# 9040_fm.net
KiCad netlist of a schematic drawn in Altium Designer
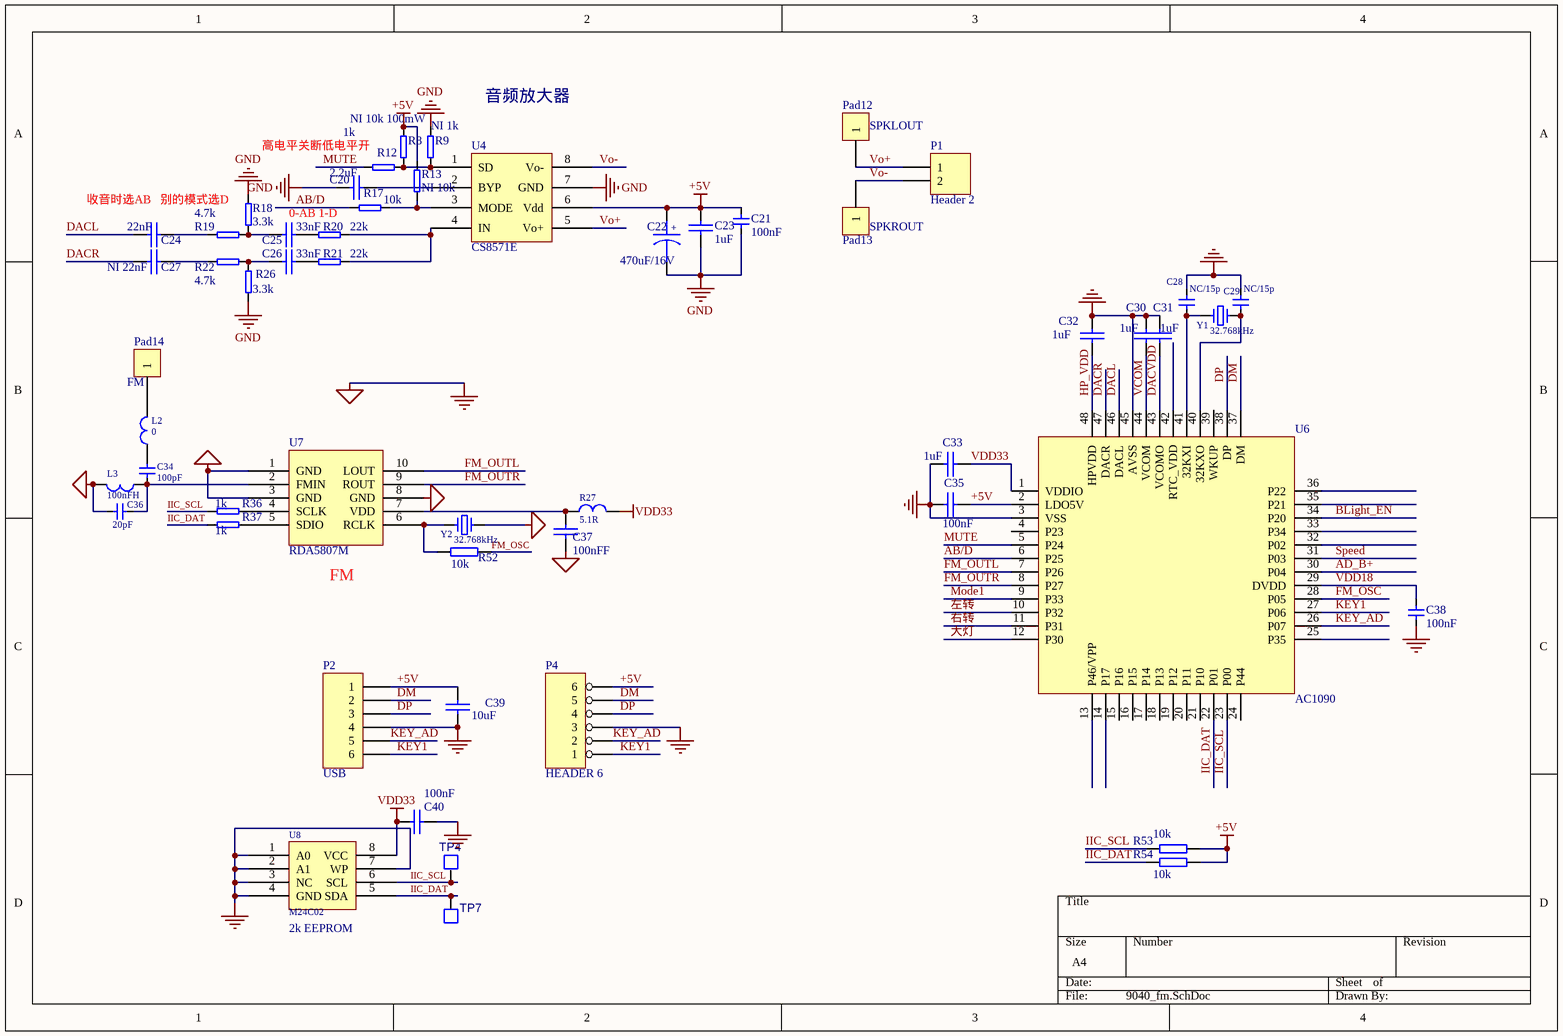
[diagram p0: 9040_fm.SchDoc]

(export (version "E")
  (design (tool "Eeschema 10.0.6"))
  (components
    (comp (ref "C20")
      (value "2.2uF")
      (footprint "0805")
      (description "Capacitor")
      (libsource (lib "") (part "CAP_1"))
    )
    (comp (ref "C21")
      (value "100nF")
      (footprint "0805")
      (description "Capacitor")
      (libsource (lib "*") (part "CAP"))
    )
    (comp (ref "C22")
      (value "470uF/16V")
      (footprint "RB.1/.2")
      (description "Capacitor")
      (libsource (lib "*") (part "CAPACITOR POL"))
    )
    (comp (ref "C23")
      (value "1uF")
      (footprint "0805")
      (description "Capacitor")
      (libsource (lib "") (part "CAP_1"))
    )
    (comp (ref "C24")
      (value "22nF")
      (footprint "0805")
      (description "Capacitor")
      (libsource (lib "") (part "CAP_1"))
    )
    (comp (ref "C25")
      (value "33nF")
      (footprint "0805")
      (description "Capacitor")
      (libsource (lib "") (part "CAP_1"))
    )
    (comp (ref "C26")
      (value "33nF")
      (footprint "0805")
      (description "Capacitor")
      (libsource (lib "") (part "CAP_1"))
    )
    (comp (ref "C27")
      (value "NI 22nF")
      (footprint "0805")
      (description "Capacitor")
      (libsource (lib "") (part "CAP_1"))
    )
    (comp (ref "C28")
      (value "NC/15p")
      (footprint "0603")
      (description "Capacitor")
      (libsource (lib "*") (part "CAP"))
    )
    (comp (ref "C29")
      (value "NC/15p")
      (footprint "0603")
      (description "Capacitor")
      (libsource (lib "*") (part "CAP"))
    )
    (comp (ref "C30")
      (value "1uF")
      (footprint "0805")
      (description "Capacitor")
      (libsource (lib "") (part "CAP_1"))
    )
    (comp (ref "C31")
      (value "1uF")
      (footprint "0805")
      (description "Capacitor")
      (libsource (lib "") (part "CAP_1"))
    )
    (comp (ref "C32")
      (value "1uF")
      (footprint "0805")
      (description "Capacitor")
      (libsource (lib "") (part "CAP_1"))
    )
    (comp (ref "C33")
      (value "1uF")
      (footprint "0805")
      (description "Capacitor")
      (libsource (lib "") (part "CAP_1"))
    )
    (comp (ref "C34")
      (value "100pF")
      (footprint "0805")
      (description "Capacitor")
      (libsource (lib "") (part "CAP_3"))
    )
    (comp (ref "C35")
      (value "100nF")
      (footprint "0805")
      (description "Capacitor")
      (libsource (lib "") (part "CAP_2"))
    )
    (comp (ref "C36")
      (value "20pF")
      (footprint "0603")
      (description "Capacitor")
      (libsource (lib "") (part "CAP_3"))
    )
    (comp (ref "C37")
      (value "100nFF")
      (footprint "0805")
      (description "Capacitor")
      (libsource (lib "") (part "CAP_1"))
    )
    (comp (ref "C38")
      (value "100nF")
      (footprint "0603")
      (description "Capacitor")
      (libsource (lib "*") (part "CAP"))
    )
    (comp (ref "C39")
      (value "10uF")
      (footprint "0805")
      (description "Capacitor")
      (libsource (lib "") (part "CAP_1"))
    )
    (comp (ref "C40")
      (value "100nF")
      (footprint "0805")
      (description "Capacitor")
      (libsource (lib "") (part "CAP_1"))
    )
    (comp (ref "L2") (value "0") (footprint "0805") (libsource (lib "*") (part "INDUCTOR")))
    (comp (ref "L3") (value "100nFH") (footprint "0603") (libsource (lib "*") (part "INDUCTOR")))
    (comp (ref "P1")
      (value "Header 2")
      (footprint "2543-WV-2PIN")
      (description "Header, 2-Pin")
      (fields (field (name "PUBLISHER") "Altium Limited"))
      (libsource (lib "Miscellaneous Connectors") (part "Header 2"))
    )
    (comp (ref "P2")
      (value "USB")
      (footprint "FPC-6")
      (description "Header, 6-Pin")
      (fields (field (name "PUBLISHER") "Altium Limited"))
      (libsource (lib "Miscellaneous Connectors") (part "Header 6"))
    )
    (comp (ref "P4") (value "HEADER 6") (footprint "HDR1X6") (libsource (lib "SchMylib1") (part "HEADER 6")))
    (comp (ref "Pad12")
      (value "SPKROUT")
      (footprint "PAD")
      (description "Connector")
      (libsource (lib "*") (part "CON1"))
    )
    (comp (ref "Pad13")
      (value "SPKLOUT")
      (footprint "PAD")
      (description "Connector")
      (libsource (lib "") (part "CON1_1"))
    )
    (comp (ref "Pad14")
      (value "FM")
      (footprint "PAD")
      (description "Connector")
      (libsource (lib "*") (part "CON1"))
    )
    (comp (ref "R8") (value "NI 10k 100mW") (footprint "0603") (libsource (lib "*") (part "RES2_1")))
    (comp (ref "R9") (value "NI 1k") (footprint "0603") (libsource (lib "*") (part "RES2_1")))
    (comp (ref "R12") (value "1k") (footprint "0603") (libsource (lib "*") (part "RES2_1")))
    (comp (ref "R13") (value "NI 10k") (footprint "0603") (libsource (lib "*") (part "RES2_1")))
    (comp (ref "R17") (value "10k") (footprint "0603") (libsource (lib "*") (part "RES2_1")))
    (comp (ref "R18") (value "3.3k") (footprint "0805") (libsource (lib "*") (part "RES2_1")))
    (comp (ref "R19") (value "4.7k") (footprint "0805") (libsource (lib "*") (part "RES2_1")))
    (comp (ref "R20") (value "22k") (footprint "0805") (libsource (lib "*") (part "RES2_1")))
    (comp (ref "R21") (value "22k") (footprint "0805") (libsource (lib "*") (part "RES2_1")))
    (comp (ref "R22") (value "4.7k") (footprint "0805") (libsource (lib "*") (part "RES2_1")))
    (comp (ref "R26") (value "3.3k") (footprint "0805") (libsource (lib "*") (part "RES2_1")))
    (comp (ref "R27") (value "5.1R") (footprint "0603") (libsource (lib "*") (part "INDUCTOR")))
    (comp (ref "R36") (value "1k") (footprint "0603") (libsource (lib "*") (part "RES2_1")))
    (comp (ref "R37") (value "1k") (footprint "0603") (libsource (lib "*") (part "RES2_1")))
    (comp (ref "R52") (value "10k") (footprint "0805") (libsource (lib "whlSCHLIB") (part "WHLRES")))
    (comp (ref "R53") (value "10k") (footprint "0603") (libsource (lib "whlSCHLIB") (part "WHLRES")))
    (comp (ref "R54") (value "10k") (footprint "0603") (libsource (lib "whlSCHLIB") (part "WHLRES")))
    (comp (ref "TP4") (value "TP50MIL") (footprint "TP50MIL") (libsource (lib "*") (part "TP50MIL")))
    (comp (ref "TP7") (value "TP50MIL") (footprint "TP50MIL") (libsource (lib "*") (part "TP50MIL")))
    (comp (ref "U4") (value "CS8571E") (footprint "SO-8") (libsource (lib "SchMylib1") (part "CS8571E")))
    (comp (ref "U6") (value "AC1090") (footprint "TQFP48 7X7") (libsource (lib "*") (part "AC1090")))
    (comp (ref "U7") (value "RDA5807M") (footprint "MSOP-10") (libsource (lib "SchMylib1") (part "RDA5807M")))
    (comp (ref "U8") (value "M24C02") (footprint "SO-8") (libsource (lib "*") (part "EEPROM-8")))
    (comp (ref "Y1") (value "32.768kHz") (footprint "CRY2060") (libsource (lib "*") (part "CRYSTAL")))
    (comp (ref "Y2") (value "32.768kHz") (footprint "CRY2060") (libsource (lib "*") (part "CRYSTAL")))
  )
  (nets
    (net (code "1") (name "+5V") (class "Default")
      (node (ref "C21") (pin "1") (pinfunction "1_1") (pintype "passive"))
      (node (ref "C22") (pin "1") (pinfunction "1_1") (pintype "passive"))
      (node (ref "C23") (pin "2") (pinfunction "2_2") (pintype "passive"))
      (node (ref "C35") (pin "2") (pinfunction "2_2") (pintype "passive"))
      (node (ref "C39") (pin "1") (pinfunction "1_1") (pintype "passive"))
      (node (ref "P2") (pin "1") (pinfunction "1_1") (pintype "passive"))
      (node (ref "P4") (pin "6") (pinfunction "6_6") (pintype "passive"))
      (node (ref "R13") (pin "2") (pinfunction "2_2") (pintype "passive"))
      (node (ref "R53") (pin "1") (pinfunction "1_1") (pintype "passive"))
      (node (ref "R54") (pin "1") (pinfunction "1_1") (pintype "passive"))
      (node (ref "R8") (pin "2") (pinfunction "2_2") (pintype "passive"))
      (node (ref "U4") (pin "6") (pinfunction "Vdd_6") (pintype "passive"))
      (node (ref "U6") (pin "2") (pinfunction "LDO5V_2") (pintype "passive"))
    )
    (net (code "2") (name "/AB{slash}D") (class "Default")
      (node (ref "R17") (pin "1") (pinfunction "1_1") (pintype "passive"))
      (node (ref "U6") (pin "6") (pinfunction "P25_6") (pintype "passive"))
    )
    (net (code "3") (name "/AD_B+") (class "Default")
      (node (ref "U6") (pin "30") (pinfunction "P04_30") (pintype "passive"))
    )
    (net (code "4") (name "/BLight_EN") (class "Default")
      (node (ref "U6") (pin "34") (pinfunction "P20_34") (pintype "passive"))
    )
    (net (code "5") (name "/DACL") (class "Default")
      (node (ref "C24") (pin "2") (pinfunction "2_2") (pintype "passive"))
      (node (ref "U6") (pin "46") (pinfunction "DACL_46") (pintype "passive"))
    )
    (net (code "6") (name "/DACR") (class "Default")
      (node (ref "C27") (pin "2") (pinfunction "2_2") (pintype "passive"))
      (node (ref "U6") (pin "47") (pinfunction "DACR_47") (pintype "passive"))
    )
    (net (code "7") (name "/DACVDD") (class "Default")
      (node (ref "C31") (pin "2") (pinfunction "2_2") (pintype "passive"))
      (node (ref "U6") (pin "43") (pinfunction "VCOMO_43") (pintype "passive"))
    )
    (net (code "8") (name "/DM") (class "Default")
      (node (ref "P2") (pin "2") (pinfunction "2_2") (pintype "passive"))
      (node (ref "P4") (pin "5") (pinfunction "5_5") (pintype "passive"))
      (node (ref "U6") (pin "37") (pinfunction "DM_37") (pintype "passive"))
    )
    (net (code "9") (name "/DP") (class "Default")
      (node (ref "P2") (pin "3") (pinfunction "3_3") (pintype "passive"))
      (node (ref "P4") (pin "4") (pinfunction "4_4") (pintype "passive"))
      (node (ref "U6") (pin "38") (pinfunction "DP_38") (pintype "passive"))
    )
    (net (code "10") (name "/FM_OSC") (class "Default")
      (node (ref "R52") (pin "1") (pinfunction "1_1") (pintype "passive"))
      (node (ref "U6") (pin "28") (pinfunction "P05_28") (pintype "passive"))
    )
    (net (code "11") (name "/FM_OUTL") (class "Default")
      (node (ref "U6") (pin "7") (pinfunction "P26_7") (pintype "passive"))
      (node (ref "U7") (pin "10") (pinfunction "LOUT_10") (pintype "passive"))
    )
    (net (code "12") (name "/FM_OUTR") (class "Default")
      (node (ref "U6") (pin "8") (pinfunction "P27_8") (pintype "passive"))
      (node (ref "U7") (pin "9") (pinfunction "ROUT_9") (pintype "passive"))
    )
    (net (code "13") (name "/HP_VDD") (class "Default")
      (node (ref "C32") (pin "2") (pinfunction "2_2") (pintype "passive"))
      (node (ref "U6") (pin "48") (pinfunction "HPVDD_48") (pintype "passive"))
    )
    (net (code "14") (name "/IIC_DAT") (class "Default")
      (node (ref "R37") (pin "1") (pinfunction "1_1") (pintype "passive"))
      (node (ref "R54") (pin "2") (pinfunction "2_2") (pintype "passive"))
      (node (ref "TP7") (pin "1") (pinfunction "1_1") (pintype "passive"))
      (node (ref "U6") (pin "22") (pinfunction "P01_22") (pintype "passive"))
      (node (ref "U8") (pin "5") (pinfunction "SDA_5") (pintype "passive"))
    )
    (net (code "15") (name "/IIC_SCL") (class "Default")
      (node (ref "R36") (pin "1") (pinfunction "1_1") (pintype "passive"))
      (node (ref "R53") (pin "2") (pinfunction "2_2") (pintype "passive"))
      (node (ref "TP4") (pin "1") (pinfunction "1_1") (pintype "passive"))
      (node (ref "U6") (pin "23") (pinfunction "P00_23") (pintype "passive"))
      (node (ref "U8") (pin "6") (pinfunction "SCL_6") (pintype "passive"))
    )
    (net (code "16") (name "/KEY1") (class "Default")
      (node (ref "P2") (pin "6") (pinfunction "6_6") (pintype "passive"))
      (node (ref "P4") (pin "1") (pinfunction "1_1") (pintype "passive"))
      (node (ref "U6") (pin "27") (pinfunction "P06_27") (pintype "passive"))
    )
    (net (code "17") (name "/KEY_AD") (class "Default")
      (node (ref "P2") (pin "5") (pinfunction "5_5") (pintype "passive"))
      (node (ref "P4") (pin "2") (pinfunction "2_2") (pintype "passive"))
      (node (ref "U6") (pin "26") (pinfunction "P07_26") (pintype "passive"))
    )
    (net (code "18") (name "/MUTE") (class "Default")
      (node (ref "R12") (pin "1") (pinfunction "1_1") (pintype "passive"))
      (node (ref "U6") (pin "5") (pinfunction "P24_5") (pintype "passive"))
    )
    (net (code "19") (name "/Mode1") (class "Default")
      (node (ref "U6") (pin "9") (pinfunction "P33_9") (pintype "passive"))
    )
    (net (code "20") (name "/Speed") (class "Default")
      (node (ref "U6") (pin "31") (pinfunction "P03_31") (pintype "passive"))
    )
    (net (code "21") (name "/VCOM") (class "Default")
      (node (ref "C30") (pin "2") (pinfunction "2_2") (pintype "passive"))
      (node (ref "U6") (pin "44") (pinfunction "VCOM_44") (pintype "passive"))
    )
    (net (code "22") (name "/VDD18") (class "Default")
      (node (ref "C38") (pin "1") (pinfunction "1_1") (pintype "passive"))
      (node (ref "U6") (pin "29") (pinfunction "DVDD_29") (pintype "passive"))
    )
    (net (code "23") (name "/Vo+") (class "Default")
      (node (ref "P1") (pin "1") (pinfunction "1_1") (pintype "passive"))
      (node (ref "Pad12") (pin "1") (pinfunction "1_1") (pintype "passive"))
      (node (ref "U4") (pin "5") (pinfunction "Vo+_5") (pintype "passive"))
    )
    (net (code "24") (name "/Vo-") (class "Default")
      (node (ref "P1") (pin "2") (pinfunction "2_2") (pintype "passive"))
      (node (ref "Pad13") (pin "1") (pinfunction "1_1") (pintype "passive"))
      (node (ref "U4") (pin "8") (pinfunction "Vo-_8") (pintype "passive"))
    )
    (net (code "25") (name "/右转") (class "Default")
      (node (ref "U6") (pin "11") (pinfunction "P31_11") (pintype "passive"))
    )
    (net (code "26") (name "/大灯") (class "Default")
      (node (ref "U6") (pin "12") (pinfunction "P30_12") (pintype "passive"))
    )
    (net (code "27") (name "/左转") (class "Default")
      (node (ref "U6") (pin "10") (pinfunction "P32_10") (pintype "passive"))
    )
    (net (code "28") (name "AGND") (class "Default")
      (node (ref "C20") (pin "2") (pinfunction "2_2") (pintype "passive"))
      (node (ref "C21") (pin "2") (pinfunction "2_2") (pintype "passive"))
      (node (ref "C22") (pin "2") (pinfunction "2_2") (pintype "passive"))
      (node (ref "C23") (pin "1") (pinfunction "1_1") (pintype "passive"))
      (node (ref "C28") (pin "2") (pinfunction "2_2") (pintype "passive"))
      (node (ref "C29") (pin "2") (pinfunction "2_2") (pintype "passive"))
      (node (ref "C30") (pin "1") (pinfunction "1_1") (pintype "passive"))
      (node (ref "C31") (pin "1") (pinfunction "1_1") (pintype "passive"))
      (node (ref "C32") (pin "1") (pinfunction "1_1") (pintype "passive"))
      (node (ref "C33") (pin "2") (pinfunction "2_2") (pintype "passive"))
      (node (ref "C35") (pin "1") (pinfunction "1_1") (pintype "passive"))
      (node (ref "C36") (pin "1") (pinfunction "1_1") (pintype "passive"))
      (node (ref "C37") (pin "2") (pinfunction "2_2") (pintype "passive"))
      (node (ref "C38") (pin "2") (pinfunction "2_2") (pintype "passive"))
      (node (ref "C39") (pin "2") (pinfunction "2_2") (pintype "passive"))
      (node (ref "C40") (pin "2") (pinfunction "2_2") (pintype "passive"))
      (node (ref "L3") (pin "2") (pinfunction "2_2") (pintype "passive"))
      (node (ref "P2") (pin "4") (pinfunction "4_4") (pintype "passive"))
      (node (ref "P4") (pin "3") (pinfunction "3_3") (pintype "passive"))
      (node (ref "R18") (pin "2") (pinfunction "2_2") (pintype "passive"))
      (node (ref "R26") (pin "1") (pinfunction "1_1") (pintype "passive"))
      (node (ref "R9") (pin "2") (pinfunction "2_2") (pintype "passive"))
      (node (ref "U4") (pin "7") (pinfunction "GND_7") (pintype "passive"))
      (node (ref "U6") (pin "3") (pinfunction "VSS_3") (pintype "passive"))
      (node (ref "U6") (pin "45") (pinfunction "AVSS_45") (pintype "passive"))
      (node (ref "U7") (pin "1") (pinfunction "GND_1") (pintype "passive"))
      (node (ref "U7") (pin "3") (pinfunction "GND_3") (pintype "passive"))
      (node (ref "U7") (pin "8") (pinfunction "GND_8") (pintype "passive"))
      (node (ref "U8") (pin "1") (pinfunction "A0_1") (pintype "passive"))
      (node (ref "U8") (pin "2") (pinfunction "A1_2") (pintype "passive"))
      (node (ref "U8") (pin "3") (pinfunction "NC_3") (pintype "passive"))
      (node (ref "U8") (pin "4") (pinfunction "GND_4") (pintype "passive"))
      (node (ref "U8") (pin "7") (pinfunction "WP_7") (pintype "passive"))
      (node (ref "Y2") (pin "1") (pinfunction "1_1") (pintype "passive"))
    )
    (net (code "29") (name "Net-(C24-Pad1)") (class "Default")
      (node (ref "C24") (pin "1") (pinfunction "1_1") (pintype "passive"))
      (node (ref "R19") (pin "1") (pinfunction "1_1") (pintype "passive"))
    )
    (net (code "30") (name "Net-(C25-Pad1)") (class "Default")
      (node (ref "C25") (pin "1") (pinfunction "1_1") (pintype "passive"))
      (node (ref "R20") (pin "2") (pinfunction "2_2") (pintype "passive"))
    )
    (net (code "31") (name "Net-(C25-Pad2)") (class "Default")
      (node (ref "C25") (pin "2") (pinfunction "2_2") (pintype "passive"))
      (node (ref "R18") (pin "1") (pinfunction "1_1") (pintype "passive"))
      (node (ref "R19") (pin "2") (pinfunction "2_2") (pintype "passive"))
    )
    (net (code "32") (name "Net-(C26-Pad1)") (class "Default")
      (node (ref "C26") (pin "1") (pinfunction "1_1") (pintype "passive"))
      (node (ref "R21") (pin "2") (pinfunction "2_2") (pintype "passive"))
    )
    (net (code "33") (name "Net-(C26-Pad2)") (class "Default")
      (node (ref "C26") (pin "2") (pinfunction "2_2") (pintype "passive"))
      (node (ref "R22") (pin "2") (pinfunction "2_2") (pintype "passive"))
      (node (ref "R26") (pin "2") (pinfunction "2_2") (pintype "passive"))
    )
    (net (code "34") (name "Net-(C27-Pad1)") (class "Default")
      (node (ref "C27") (pin "1") (pinfunction "1_1") (pintype "passive"))
      (node (ref "R22") (pin "1") (pinfunction "1_1") (pintype "passive"))
    )
    (net (code "35") (name "Net-(C34-Pad2)") (class "Default")
      (node (ref "C34") (pin "2") (pinfunction "2_2") (pintype "passive"))
      (node (ref "L2") (pin "1") (pinfunction "1_1") (pintype "passive"))
    )
    (net (code "36") (name "Net-(L2-Pad2)") (class "Default")
      (node (ref "L2") (pin "2") (pinfunction "2_2") (pintype "passive"))
      (node (ref "Pad14") (pin "1") (pinfunction "1_1") (pintype "passive"))
    )
    (net (code "37") (name "Net-(U4-BYP)") (class "Default")
      (node (ref "C20") (pin "1") (pinfunction "1_1") (pintype "passive"))
      (node (ref "U4") (pin "2") (pinfunction "BYP_2") (pintype "passive"))
    )
    (net (code "38") (name "Net-(U4-IN)") (class "Default")
      (node (ref "R20") (pin "1") (pinfunction "1_1") (pintype "passive"))
      (node (ref "R21") (pin "1") (pinfunction "1_1") (pintype "passive"))
      (node (ref "U4") (pin "4") (pinfunction "IN_4") (pintype "passive"))
    )
    (net (code "39") (name "Net-(U4-MODE)") (class "Default")
      (node (ref "R13") (pin "1") (pinfunction "1_1") (pintype "passive"))
      (node (ref "R17") (pin "2") (pinfunction "2_2") (pintype "passive"))
      (node (ref "U4") (pin "3") (pinfunction "MODE_3") (pintype "passive"))
    )
    (net (code "40") (name "Net-(U4-SD)") (class "Default")
      (node (ref "R12") (pin "2") (pinfunction "2_2") (pintype "passive"))
      (node (ref "R8") (pin "1") (pinfunction "1_1") (pintype "passive"))
      (node (ref "R9") (pin "1") (pinfunction "1_1") (pintype "passive"))
      (node (ref "U4") (pin "1") (pinfunction "SD_1") (pintype "passive"))
    )
    (net (code "41") (name "Net-(U6-32KXI)") (class "Default")
      (node (ref "C28") (pin "1") (pinfunction "1_1") (pintype "passive"))
      (node (ref "U6") (pin "41") (pinfunction "32KXI_41") (pintype "passive"))
      (node (ref "Y1") (pin "2") (pinfunction "2_2") (pintype "passive"))
    )
    (net (code "42") (name "Net-(U6-32KXO)") (class "Default")
      (node (ref "C29") (pin "1") (pinfunction "1_1") (pintype "passive"))
      (node (ref "U6") (pin "40") (pinfunction "32KXO_40") (pintype "passive"))
      (node (ref "Y1") (pin "1") (pinfunction "1_1") (pintype "passive"))
    )
    (net (code "43") (name "Net-(U7-FMIN)") (class "Default")
      (node (ref "C34") (pin "1") (pinfunction "1_1") (pintype "passive"))
      (node (ref "C36") (pin "2") (pinfunction "2_2") (pintype "passive"))
      (node (ref "L3") (pin "1") (pinfunction "1_1") (pintype "passive"))
      (node (ref "U7") (pin "2") (pinfunction "FMIN_2") (pintype "passive"))
    )
    (net (code "44") (name "Net-(U7-RCLK)") (class "Default")
      (node (ref "R52") (pin "2") (pinfunction "2_2") (pintype "passive"))
      (node (ref "U7") (pin "6") (pinfunction "RCLK_6") (pintype "passive"))
      (node (ref "Y2") (pin "2") (pinfunction "2_2") (pintype "passive"))
    )
    (net (code "45") (name "Net-(U7-SCLK)") (class "Default")
      (node (ref "R36") (pin "2") (pinfunction "2_2") (pintype "passive"))
      (node (ref "U7") (pin "4") (pinfunction "SCLK_4") (pintype "passive"))
    )
    (net (code "46") (name "Net-(U7-SDIO)") (class "Default")
      (node (ref "R37") (pin "2") (pinfunction "2_2") (pintype "passive"))
      (node (ref "U7") (pin "5") (pinfunction "SDIO_5") (pintype "passive"))
    )
    (net (code "47") (name "Net-(U7-VDD)") (class "Default")
      (node (ref "C37") (pin "1") (pinfunction "1_1") (pintype "passive"))
      (node (ref "R27") (pin "1") (pinfunction "1_1") (pintype "passive"))
      (node (ref "U7") (pin "7") (pinfunction "VDD_7") (pintype "passive"))
    )
    (net (code "48") (name "VDD33") (class "Default")
      (node (ref "C33") (pin "1") (pinfunction "1_1") (pintype "passive"))
      (node (ref "C40") (pin "1") (pinfunction "1_1") (pintype "passive"))
      (node (ref "R27") (pin "2") (pinfunction "2_2") (pintype "passive"))
      (node (ref "U6") (pin "1") (pinfunction "VDDIO_1") (pintype "passive"))
      (node (ref "U8") (pin "8") (pinfunction "VCC_8") (pintype "passive"))
    )
    (net (code "49") (name "unconnected-(U6-P02-Pad32)") (class "Default")
      (node (ref "U6") (pin "32") (pinfunction "P02_32") (pintype "passive"))
    )
    (net (code "50") (name "unconnected-(U6-P10-Pad21)") (class "Default")
      (node (ref "U6") (pin "21") (pinfunction "P10_21") (pintype "passive"))
    )
    (net (code "51") (name "unconnected-(U6-P11-Pad20)") (class "Default")
      (node (ref "U6") (pin "20") (pinfunction "P11_20") (pintype "passive"))
    )
    (net (code "52") (name "unconnected-(U6-P12-Pad19)") (class "Default")
      (node (ref "U6") (pin "19") (pinfunction "P12_19") (pintype "passive"))
    )
    (net (code "53") (name "unconnected-(U6-P13-Pad18)") (class "Default")
      (node (ref "U6") (pin "18") (pinfunction "P13_18") (pintype "passive"))
    )
    (net (code "54") (name "unconnected-(U6-P14-Pad17)") (class "Default")
      (node (ref "U6") (pin "17") (pinfunction "P14_17") (pintype "passive"))
    )
    (net (code "55") (name "unconnected-(U6-P15-Pad16)") (class "Default")
      (node (ref "U6") (pin "16") (pinfunction "P15_16") (pintype "passive"))
    )
    (net (code "56") (name "unconnected-(U6-P16-Pad15)") (class "Default")
      (node (ref "U6") (pin "15") (pinfunction "P16_15") (pintype "passive"))
    )
    (net (code "57") (name "unconnected-(U6-P17-Pad14)") (class "Default")
      (node (ref "U6") (pin "14") (pinfunction "P17_14") (pintype "passive"))
    )
    (net (code "58") (name "unconnected-(U6-P21-Pad35)") (class "Default")
      (node (ref "U6") (pin "35") (pinfunction "P21_35") (pintype "passive"))
    )
    (net (code "59") (name "unconnected-(U6-P22-Pad36)") (class "Default")
      (node (ref "U6") (pin "36") (pinfunction "P22_36") (pintype "passive"))
    )
    (net (code "60") (name "unconnected-(U6-P23-Pad4)") (class "Default")
      (node (ref "U6") (pin "4") (pinfunction "P23_4") (pintype "passive"))
    )
    (net (code "61") (name "unconnected-(U6-P34-Pad33)") (class "Default")
      (node (ref "U6") (pin "33") (pinfunction "P34_33") (pintype "passive"))
    )
    (net (code "62") (name "unconnected-(U6-P35-Pad25)") (class "Default")
      (node (ref "U6") (pin "25") (pinfunction "P35_25") (pintype "passive"))
    )
    (net (code "63") (name "unconnected-(U6-P44-Pad24)") (class "Default")
      (node (ref "U6") (pin "24") (pinfunction "P44_24") (pintype "passive"))
    )
    (net (code "64") (name "unconnected-(U6-P46{slash}VPP-Pad13)") (class "Default")
      (node (ref "U6") (pin "13") (pinfunction "P46/VPP_13") (pintype "passive"))
    )
    (net (code "65") (name "unconnected-(U6-RTC_VDD-Pad42)") (class "Default")
      (node (ref "U6") (pin "42") (pinfunction "RTC_VDD_42") (pintype "passive"))
    )
    (net (code "66") (name "unconnected-(U6-WKUP-Pad39)") (class "Default")
      (node (ref "U6") (pin "39") (pinfunction "WKUP_39") (pintype "passive"))
    )
  )
)
